# OTHER_PARTS.net
KiCad netlist of a schematic drawn in Altium Designer
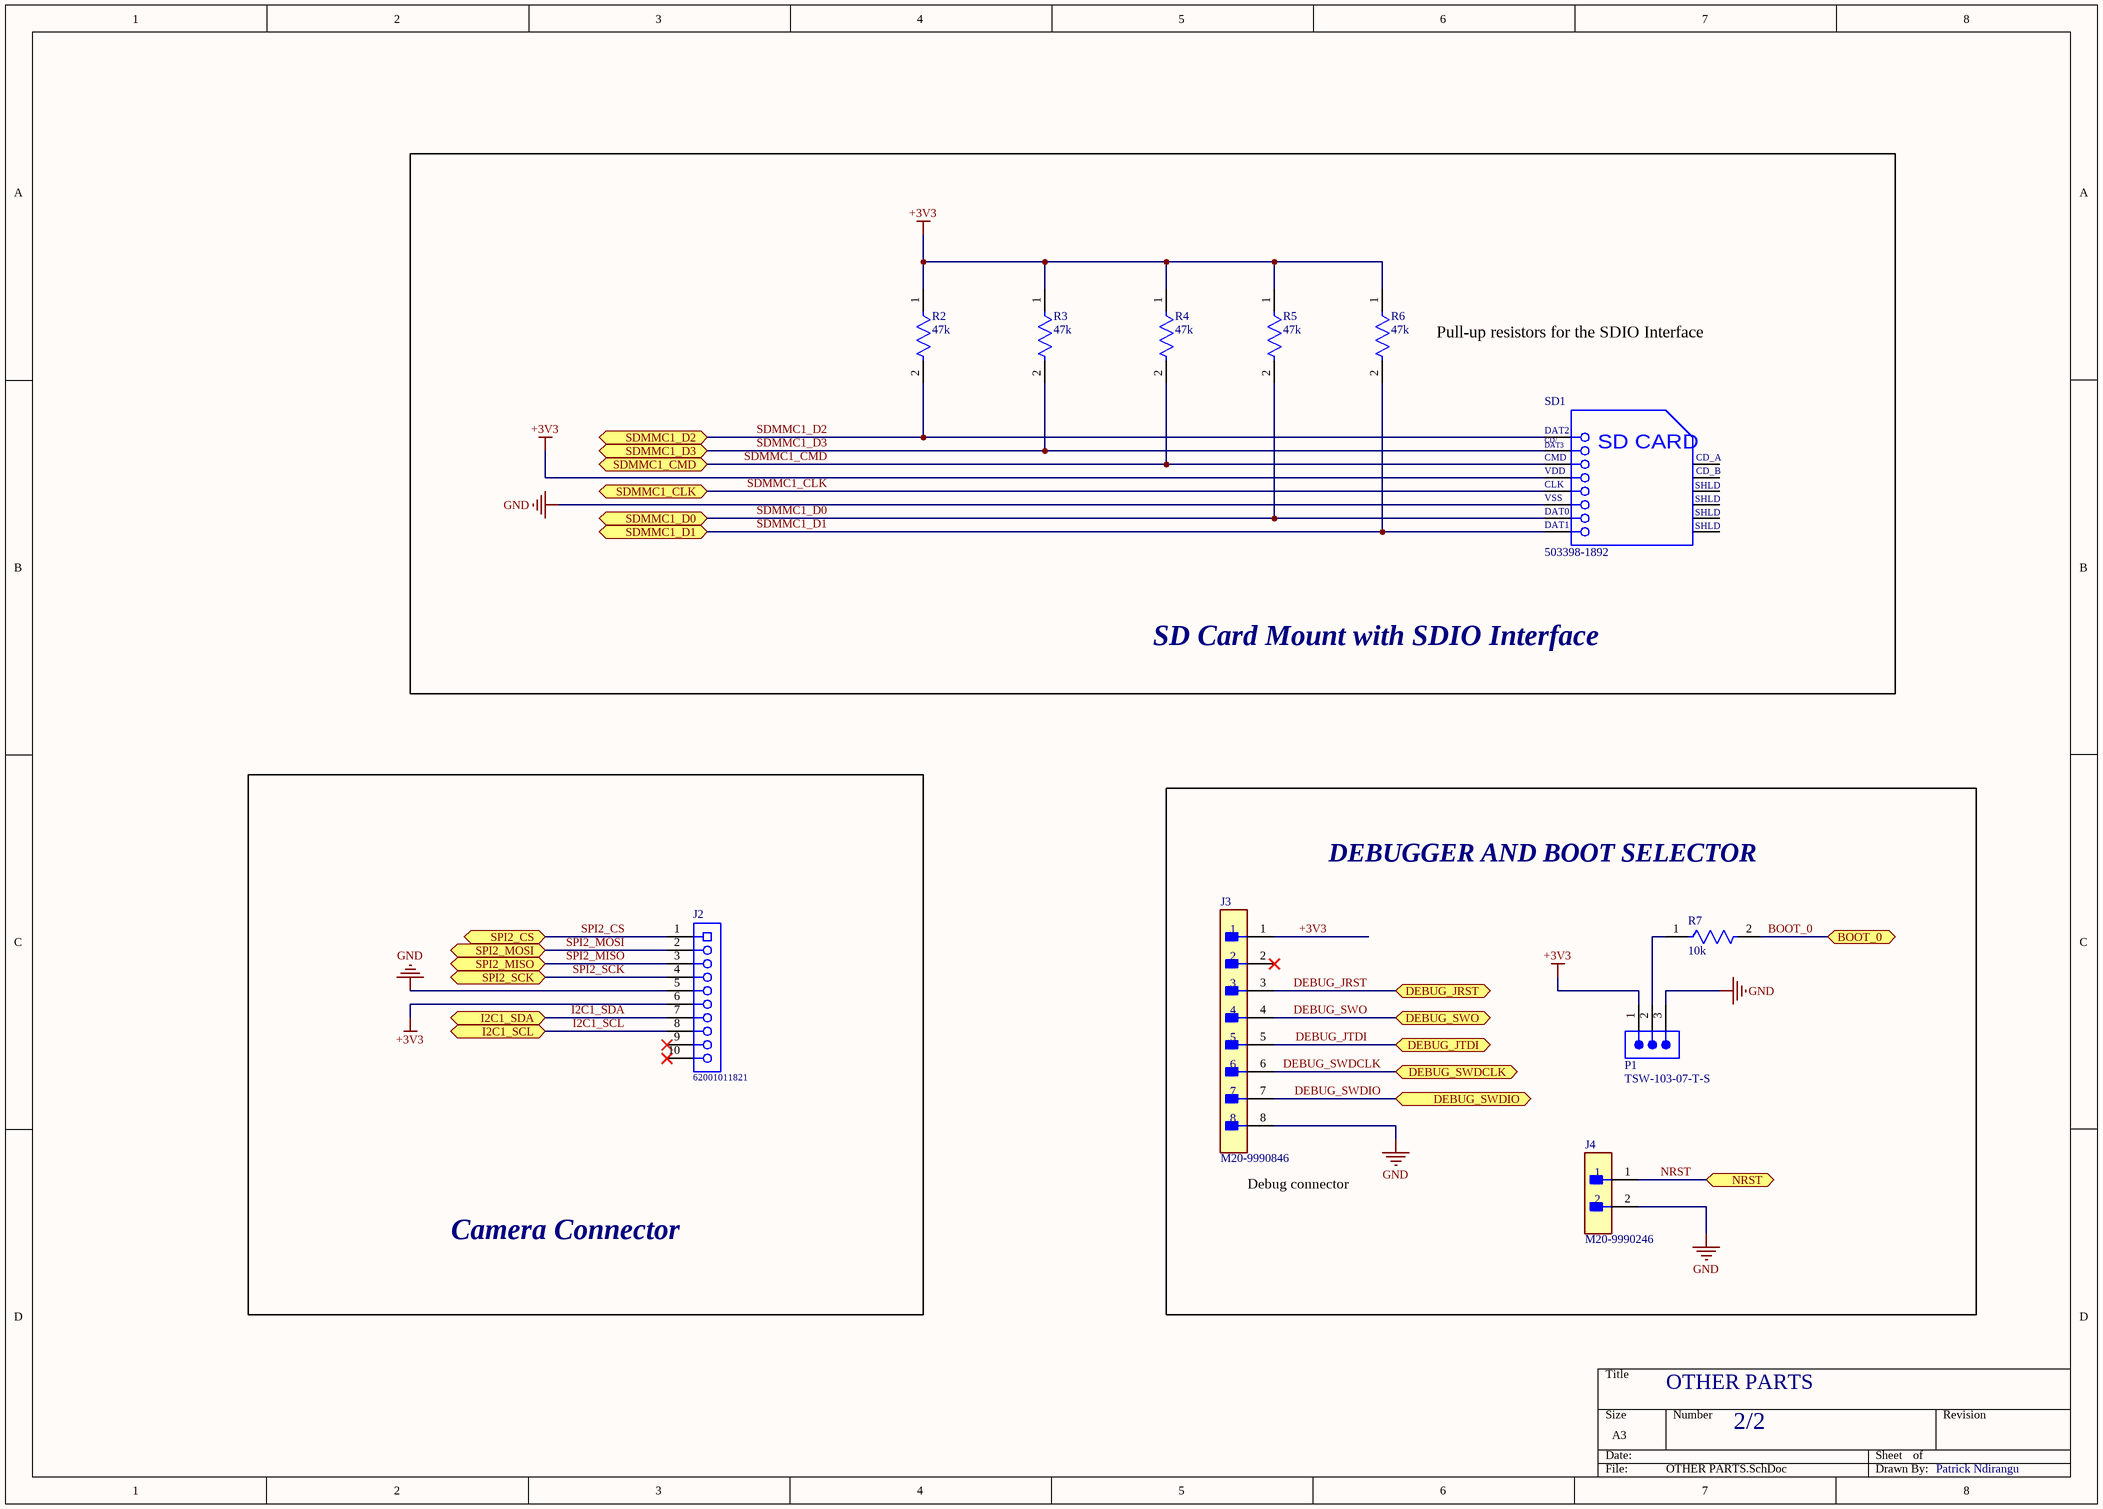
[diagram p0: OTHER PARTS.SchDoc]

(export (version "E")
  (design (tool "Eeschema 10.0.6"))
  (components
    (comp (ref "J2")
      (value "62001011821")
      (footprint "62001011821")
      (description "THT Vertical Socket Header WR-PHD, Pitch 2.00 mm, Single Row, 10 pins")
      (fields (field (name "MANUFACTURER") "Wurth Elektronik") (field (name "PUBLISHER") "WurthElektronik"))
      (libsource (lib "Altium Content Vault") (part "WE-CN-1P-F-R10"))
    )
    (comp (ref "J3")
      (value "M20-9990846")
      (footprint "FP-M20-9990846-MFG")
      (description "CONN HEADER VERT 8POS 2.54MM")
      (libsource (lib "Altium Content Vault") (part "99ec2b232beb5d2356d4d77f6a047f0"))
    )
    (comp (ref "J4")
      (value "M20-9990246")
      (footprint "FP-M20-9990246-MFG")
      (description "CONN HEADER VERT 2POS 2.54MM")
      (fields
        (field (name "OCTOPART") "https://octopart.com/m20-9990246-harwin-2590635")
        (field (name "MANUFACTURER") "Harwin")
      )
      (libsource (lib "Altium Content Vault") (part "3bc925449376181038e59eaffc5286c"))
    )
    (comp (ref "P1")
      (value "TSW-103-07-T-S")
      (footprint "SMTC-TSW-103-07-X-S")
      (description "0.025\" SQ Post Header, Through-hole, Vertical, -55 to 105 degC, 2.54 mm Pitch, 3-Pin, Male, RoHS")
      (fields (field (name "MANUFACTURER") "Samtec"))
      (libsource (lib "Altium Content Vault") (part "SMTC-TSW-103-X-X-S-X"))
    )
    (comp (ref "R2")
      (value "47k")
      (footprint "FP-KTR03-IPC_C")
      (description "Res Thick Film 0603 47kΩ 1% 0.1W ±100ppm/°C Automotive Paper T/R")
      (fields (field (name "TOLERANCE") "1%"))
      (libsource (lib "Altium Content Vault") (part "1029c3af85768c4190bb7ad29bc67b5"))
    )
    (comp (ref "R3")
      (value "47k")
      (footprint "FP-KTR03-IPC_C")
      (description "Res Thick Film 0603 47kΩ 1% 0.1W ±100ppm/°C Automotive Paper T/R")
      (fields (field (name "TOLERANCE") "1%"))
      (libsource (lib "Altium Content Vault") (part "1029c3af85768c4190bb7ad29bc67b5"))
    )
    (comp (ref "R4")
      (value "47k")
      (footprint "FP-KTR03-IPC_C")
      (description "Res Thick Film 0603 47kΩ 1% 0.1W ±100ppm/°C Automotive Paper T/R")
      (fields (field (name "TOLERANCE") "1%"))
      (libsource (lib "Altium Content Vault") (part "1029c3af85768c4190bb7ad29bc67b5"))
    )
    (comp (ref "R5")
      (value "47k")
      (footprint "FP-KTR03-IPC_C")
      (description "Res Thick Film 0603 47kΩ 1% 0.1W ±100ppm/°C Automotive Paper T/R")
      (fields (field (name "TOLERANCE") "1%"))
      (libsource (lib "Altium Content Vault") (part "1029c3af85768c4190bb7ad29bc67b5"))
    )
    (comp (ref "R6")
      (value "47k")
      (footprint "FP-KTR03-IPC_C")
      (description "Res Thick Film 0603 47kΩ 1% 0.1W ±100ppm/°C Automotive Paper T/R")
      (fields (field (name "TOLERANCE") "1%"))
      (libsource (lib "Altium Content Vault") (part "1029c3af85768c4190bb7ad29bc67b5"))
    )
    (comp (ref "R7")
      (value "10k")
      (footprint "FP-SFR03-MFG")
      (description "RES SMD 10K OHM 1% 1/10W 0603")
      (libsource (lib "Altium Content Vault") (part "1029c3af85768c4190bb7ad29bc67b5"))
    )
    (comp (ref "SD1")
      (value "503398-1892")
      (footprint "MOLX-503398-1892_V")
      (description "Micro SD Connector, Pitch 1.1 mm, 8 Position, Height 1.4 mm, -25 to 85 degC, RoHS, Tape and Reel")
      (fields (field (name "MANUFACTURER") "Molex"))
      (libsource (lib "Altium Content Vault") (part "CN-SD-8-2SW-4S"))
    )
  )
  (nets
    (net (code "1") (name "+3V3") (class "Default")
      (node (ref "J2") (pin "6") (pinfunction "6_6") (pintype "passive"))
      (node (ref "J3") (pin "1") (pinfunction "1_1") (pintype "passive"))
      (node (ref "P1") (pin "1") (pinfunction "1_1") (pintype "passive"))
      (node (ref "R2") (pin "1") (pinfunction "1_1") (pintype "passive"))
      (node (ref "R3") (pin "1") (pinfunction "1_1") (pintype "passive"))
      (node (ref "R4") (pin "1") (pinfunction "1_1") (pintype "passive"))
      (node (ref "R5") (pin "1") (pinfunction "1_1") (pintype "passive"))
      (node (ref "R6") (pin "1") (pinfunction "1_1") (pintype "passive"))
      (node (ref "SD1") (pin "4") (pinfunction "VDD_4") (pintype "passive"))
    )
    (net (code "2") (name "/BOOT_0") (class "Default")
      (node (ref "R7") (pin "2") (pinfunction "2_2") (pintype "passive"))
    )
    (net (code "3") (name "/DEBUG_JRST") (class "Default")
      (node (ref "J3") (pin "3") (pinfunction "3_3") (pintype "passive"))
    )
    (net (code "4") (name "/DEBUG_JTDI") (class "Default")
      (node (ref "J3") (pin "5") (pinfunction "5_5") (pintype "passive"))
    )
    (net (code "5") (name "/DEBUG_SWDCLK") (class "Default")
      (node (ref "J3") (pin "6") (pinfunction "6_6") (pintype "passive"))
    )
    (net (code "6") (name "/DEBUG_SWDIO") (class "Default")
      (node (ref "J3") (pin "7") (pinfunction "7_7") (pintype "passive"))
    )
    (net (code "7") (name "/DEBUG_SWO") (class "Default")
      (node (ref "J3") (pin "4") (pinfunction "4_4") (pintype "passive"))
    )
    (net (code "8") (name "/I2C1_SCL") (class "Default")
      (node (ref "J2") (pin "8") (pinfunction "8_8") (pintype "passive"))
    )
    (net (code "9") (name "/I2C1_SDA") (class "Default")
      (node (ref "J2") (pin "7") (pinfunction "7_7") (pintype "passive"))
    )
    (net (code "10") (name "/NRST") (class "Default")
      (node (ref "J4") (pin "1") (pinfunction "1_1") (pintype "passive"))
    )
    (net (code "11") (name "/SDMMC1_CLK") (class "Default")
      (node (ref "SD1") (pin "5") (pinfunction "CLK_5") (pintype "passive"))
    )
    (net (code "12") (name "/SDMMC1_CMD") (class "Default")
      (node (ref "R4") (pin "2") (pinfunction "2_2") (pintype "passive"))
      (node (ref "SD1") (pin "3") (pinfunction "CMD_3") (pintype "passive"))
    )
    (net (code "13") (name "/SDMMC1_D0") (class "Default")
      (node (ref "R5") (pin "2") (pinfunction "2_2") (pintype "passive"))
      (node (ref "SD1") (pin "7") (pinfunction "DAT0_7") (pintype "passive"))
    )
    (net (code "14") (name "/SDMMC1_D1") (class "Default")
      (node (ref "R6") (pin "2") (pinfunction "2_2") (pintype "passive"))
      (node (ref "SD1") (pin "8") (pinfunction "DAT1_8") (pintype "passive"))
    )
    (net (code "15") (name "/SDMMC1_D2") (class "Default")
      (node (ref "R2") (pin "2") (pinfunction "2_2") (pintype "passive"))
      (node (ref "SD1") (pin "1") (pinfunction "DAT2_1") (pintype "passive"))
    )
    (net (code "16") (name "/SDMMC1_D3") (class "Default")
      (node (ref "R3") (pin "2") (pinfunction "2_2") (pintype "passive"))
      (node (ref "SD1") (pin "2") (pinfunction "CD/DAT3_2") (pintype "passive"))
    )
    (net (code "17") (name "/SPI2_CS") (class "Default")
      (node (ref "J2") (pin "1") (pinfunction "1_1") (pintype "passive"))
    )
    (net (code "18") (name "/SPI2_MISO") (class "Default")
      (node (ref "J2") (pin "3") (pinfunction "3_3") (pintype "passive"))
    )
    (net (code "19") (name "/SPI2_MOSI") (class "Default")
      (node (ref "J2") (pin "2") (pinfunction "2_2") (pintype "passive"))
    )
    (net (code "20") (name "/SPI2_SCK") (class "Default")
      (node (ref "J2") (pin "4") (pinfunction "4_4") (pintype "passive"))
    )
    (net (code "21") (name "GND") (class "Default")
      (node (ref "J2") (pin "5") (pinfunction "5_5") (pintype "passive"))
      (node (ref "J3") (pin "8") (pinfunction "8_8") (pintype "passive"))
      (node (ref "J4") (pin "2") (pinfunction "2_2") (pintype "passive"))
      (node (ref "P1") (pin "3") (pinfunction "3_3") (pintype "passive"))
      (node (ref "SD1") (pin "6") (pinfunction "VSS_6") (pintype "passive"))
    )
    (net (code "22") (name "Net-(P1-Pad2)") (class "Default")
      (node (ref "P1") (pin "2") (pinfunction "2_2") (pintype "passive"))
      (node (ref "R7") (pin "1") (pinfunction "1_1") (pintype "passive"))
    )
    (net (code "23") (name "unconnected-(J2-Pad9)") (class "Default")
      (node (ref "J2") (pin "9") (pinfunction "9_9") (pintype "passive+no_connect"))
    )
    (net (code "24") (name "unconnected-(J2-Pad10)") (class "Default")
      (node (ref "J2") (pin "10") (pinfunction "10_10") (pintype "passive+no_connect"))
    )
    (net (code "25") (name "unconnected-(J3-Pad2)") (class "Default")
      (node (ref "J3") (pin "2") (pinfunction "2_2") (pintype "passive+no_connect"))
    )
    (net (code "26") (name "unconnected-(SD1-CD_A-Pad9)") (class "Default")
      (node (ref "SD1") (pin "9") (pinfunction "CD_A_9") (pintype "passive"))
    )
    (net (code "27") (name "unconnected-(SD1-CD_B-Pad10)") (class "Default")
      (node (ref "SD1") (pin "10") (pinfunction "CD_B_10") (pintype "passive"))
    )
    (net (code "28") (name "unconnected-(SD1-SHLD-Pad11)") (class "Default")
      (node (ref "SD1") (pin "11") (pinfunction "SHLD_11") (pintype "passive"))
    )
    (net (code "29") (name "unconnected-(SD1-SHLD-Pad12)") (class "Default")
      (node (ref "SD1") (pin "12") (pinfunction "SHLD_12") (pintype "passive"))
    )
    (net (code "30") (name "unconnected-(SD1-SHLD-Pad13)") (class "Default")
      (node (ref "SD1") (pin "13") (pinfunction "SHLD_13") (pintype "passive"))
    )
    (net (code "31") (name "unconnected-(SD1-SHLD-Pad14)") (class "Default")
      (node (ref "SD1") (pin "14") (pinfunction "SHLD_14") (pintype "passive"))
    )
  )
)
